# flossjtag.net
KiCad netlist of a schematic drawn in EAGLE
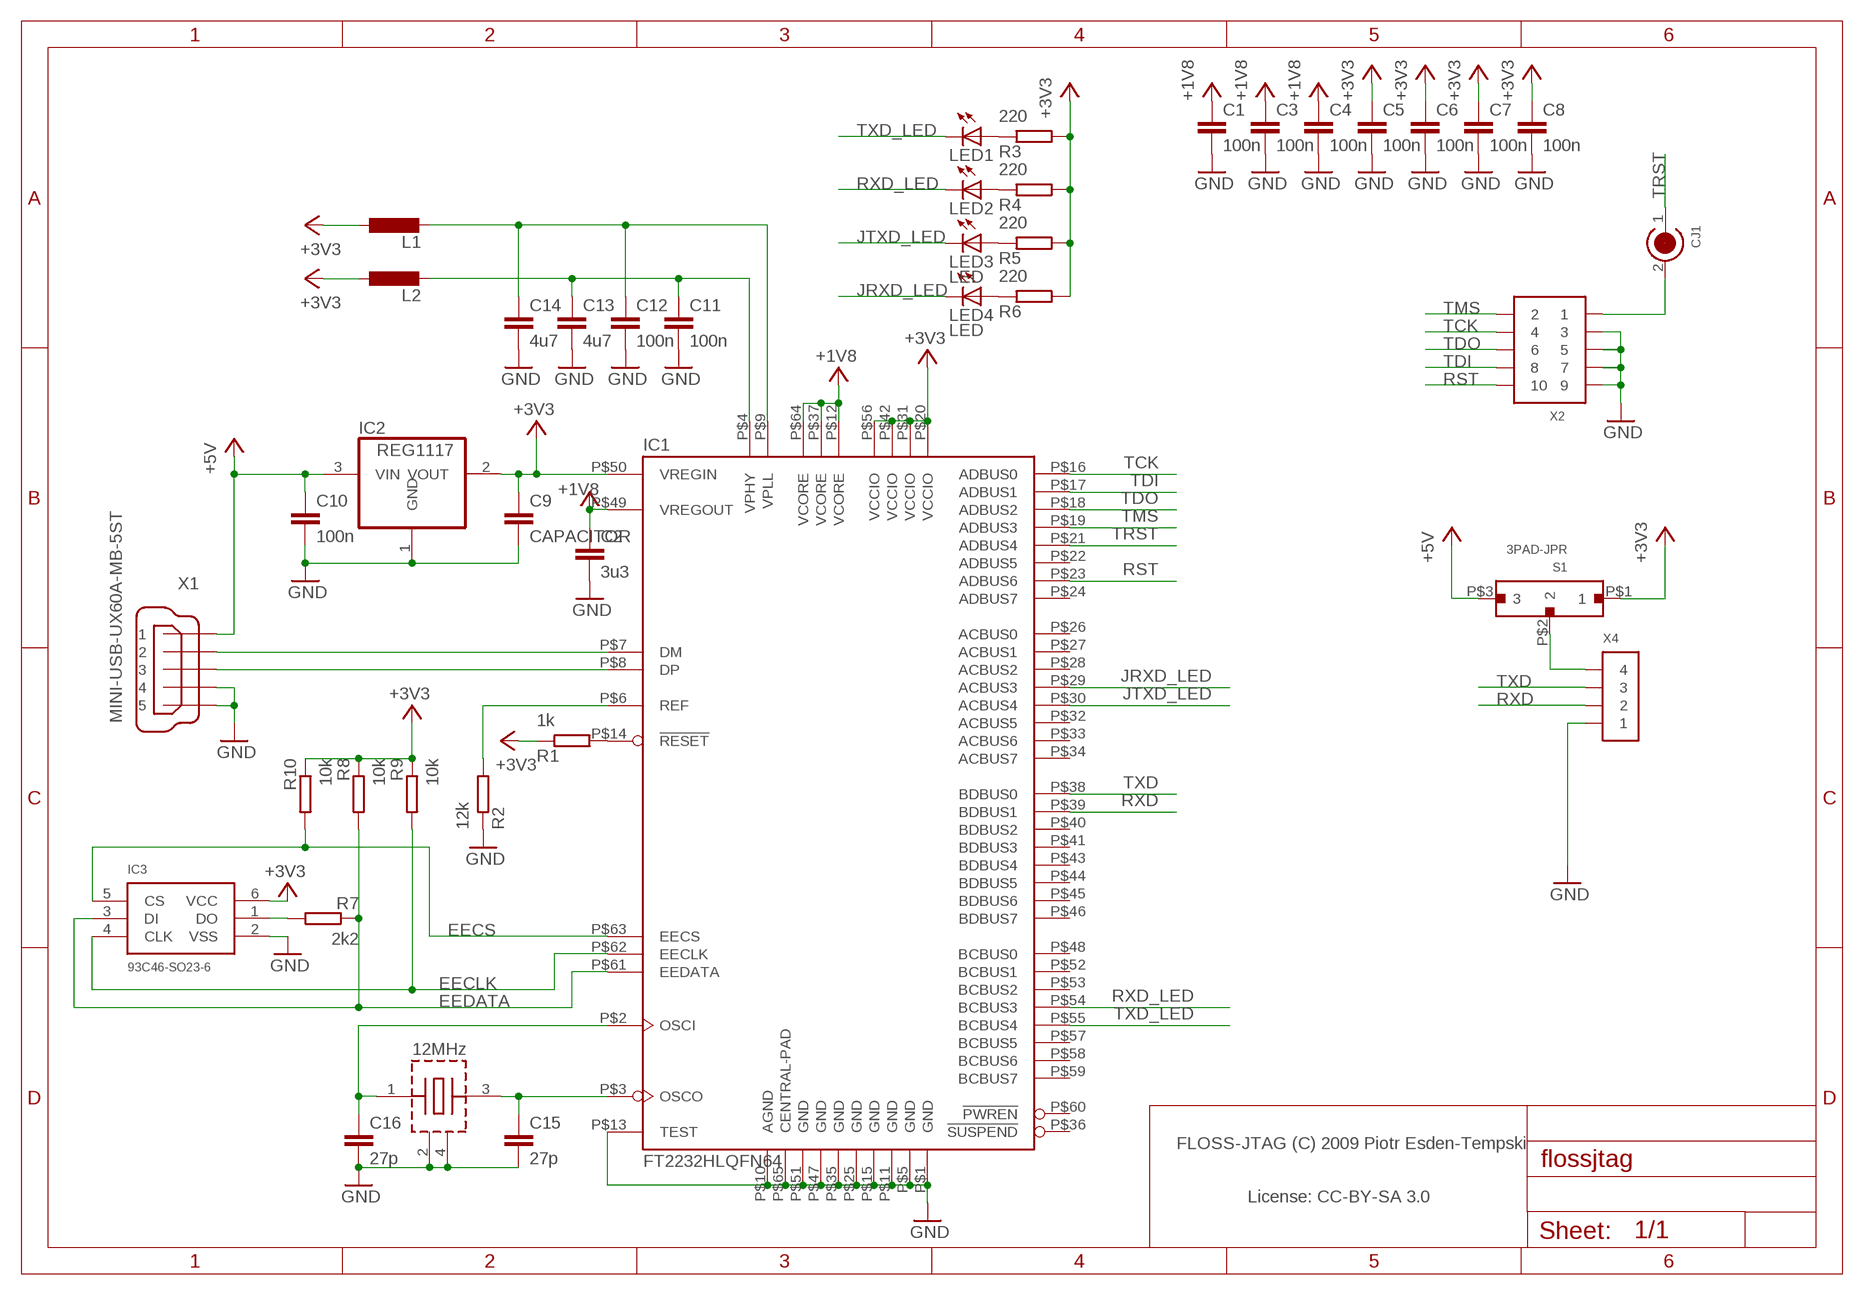
[diagram p0: schematic, sheet 1]

(export (version "E")
  (design (tool "Eeschema 10.0.6"))
  (components
    (comp (ref "C1")
      (value "100n")
      (footprint "eagle-import:0603-CAP")
      (libsource (lib "eagle-import") (part "CAPACITOR-0603"))
    )
    (comp (ref "C2")
      (value "3u3")
      (footprint "eagle-import:0603-CAP")
      (libsource (lib "eagle-import") (part "CAPACITOR-0603"))
    )
    (comp (ref "C3")
      (value "100n")
      (footprint "eagle-import:0603-CAP")
      (libsource (lib "eagle-import") (part "CAPACITOR-0603"))
    )
    (comp (ref "C4")
      (value "100n")
      (footprint "eagle-import:0603-CAP")
      (libsource (lib "eagle-import") (part "CAPACITOR-0603"))
    )
    (comp (ref "C5")
      (value "100n")
      (footprint "eagle-import:0603-CAP")
      (libsource (lib "eagle-import") (part "CAPACITOR-0603"))
    )
    (comp (ref "C6")
      (value "100n")
      (footprint "eagle-import:0603-CAP")
      (libsource (lib "eagle-import") (part "CAPACITOR-0603"))
    )
    (comp (ref "C7")
      (value "100n")
      (footprint "eagle-import:0603-CAP")
      (libsource (lib "eagle-import") (part "CAPACITOR-0603"))
    )
    (comp (ref "C8")
      (value "100n")
      (footprint "eagle-import:0603-CAP")
      (libsource (lib "eagle-import") (part "CAPACITOR-0603"))
    )
    (comp (ref "C9")
      (value "CAPACITOR")
      (footprint "eagle-import:0603-CAP")
      (libsource (lib "eagle-import") (part "CAPACITOR"))
    )
    (comp (ref "C10")
      (value "100n")
      (footprint "eagle-import:0603-CAP")
      (libsource (lib "eagle-import") (part "CAPACITOR"))
    )
    (comp (ref "C11")
      (value "100n")
      (footprint "eagle-import:0603-CAP")
      (libsource (lib "eagle-import") (part "CAPACITOR-0603"))
    )
    (comp (ref "C12")
      (value "100n")
      (footprint "eagle-import:0603-CAP")
      (libsource (lib "eagle-import") (part "CAPACITOR-0603"))
    )
    (comp (ref "C13")
      (value "4u7")
      (footprint "eagle-import:0603-CAP")
      (libsource (lib "eagle-import") (part "CAPACITOR-0603"))
    )
    (comp (ref "C14")
      (value "4u7")
      (footprint "eagle-import:0603-CAP")
      (libsource (lib "eagle-import") (part "CAPACITOR-0603"))
    )
    (comp (ref "C15")
      (value "27p")
      (footprint "eagle-import:0603-CAP")
      (libsource (lib "eagle-import") (part "CAPACITOR"))
    )
    (comp (ref "C16")
      (value "27p")
      (footprint "eagle-import:0603-CAP")
      (libsource (lib "eagle-import") (part "CAPACITOR"))
    )
    (comp (ref "CJ1")
      (value "CIRC_JMP")
      (footprint "eagle-import:CIRC_JMP")
      (libsource (lib "eagle-import") (part "CIRC_JMP"))
    )
    (comp (ref "IC1")
      (value "FT2232HLQFN64")
      (footprint "eagle-import:QFN64")
      (libsource (lib "eagle-import") (part "FT2232HLQFN64"))
    )
    (comp (ref "IC2")
      (value "REG1117")
      (footprint "eagle-import:SOT223")
      (libsource (lib "eagle-import") (part "REG1117"))
    )
    (comp (ref "IC3")
      (value "93C46-SO23-6")
      (footprint "eagle-import:SO23-6")
      (libsource (lib "eagle-import") (part "93C46-SO23-6"))
    )
    (comp (ref "L1")
      (value "INDUCTOR-0603")
      (footprint "eagle-import:0603-IND")
      (libsource (lib "eagle-import") (part "INDUCTOR-0603"))
    )
    (comp (ref "L2")
      (value "INDUCTOR-0603")
      (footprint "eagle-import:0603-IND")
      (libsource (lib "eagle-import") (part "INDUCTOR-0603"))
    )
    (comp (ref "LED1")
      (value "LED")
      (footprint "eagle-import:0603-LED")
      (libsource (lib "eagle-import") (part "LED"))
    )
    (comp (ref "LED2")
      (value "LED")
      (footprint "eagle-import:0603-LED")
      (libsource (lib "eagle-import") (part "LED"))
    )
    (comp (ref "LED3")
      (value "LED")
      (footprint "eagle-import:0603-LED")
      (libsource (lib "eagle-import") (part "LED"))
    )
    (comp (ref "LED4")
      (value "LED")
      (footprint "eagle-import:0603-LED")
      (libsource (lib "eagle-import") (part "LED"))
    )
    (comp (ref "R1")
      (value "1k")
      (footprint "eagle-import:0603-RES")
      (libsource (lib "eagle-import") (part "RESISTOR-0603"))
    )
    (comp (ref "R2")
      (value "12k")
      (footprint "eagle-import:0603-RES")
      (libsource (lib "eagle-import") (part "RESISTOR-0603"))
    )
    (comp (ref "R3")
      (value "220")
      (footprint "eagle-import:0603-RES")
      (libsource (lib "eagle-import") (part "RESISTOR-0603"))
    )
    (comp (ref "R4")
      (value "220")
      (footprint "eagle-import:0603-RES")
      (libsource (lib "eagle-import") (part "RESISTOR-0603"))
    )
    (comp (ref "R5")
      (value "220")
      (footprint "eagle-import:0603-RES")
      (libsource (lib "eagle-import") (part "RESISTOR-0603"))
    )
    (comp (ref "R6")
      (value "220")
      (footprint "eagle-import:0603-RES")
      (libsource (lib "eagle-import") (part "RESISTOR-0603"))
    )
    (comp (ref "R7")
      (value "2k2")
      (footprint "eagle-import:0603-RES")
      (libsource (lib "eagle-import") (part "RESISTOR-0603"))
    )
    (comp (ref "R8")
      (value "10k")
      (footprint "eagle-import:0603-RES")
      (libsource (lib "eagle-import") (part "RESISTOR-0603"))
    )
    (comp (ref "R9")
      (value "10k")
      (footprint "eagle-import:0603-RES")
      (libsource (lib "eagle-import") (part "RESISTOR-0603"))
    )
    (comp (ref "R10")
      (value "10k")
      (footprint "eagle-import:0603-RES")
      (libsource (lib "eagle-import") (part "RESISTOR-0603"))
    )
    (comp (ref "S1")
      (value "3PAD-JPR")
      (footprint "eagle-import:SW-JS102000SAQN")
      (libsource (lib "eagle-import") (part "3PAD-JPR"))
    )
    (comp (ref "X1")
      (value "MINI-USB-UX60A-MB-5ST")
      (footprint "eagle-import:UX60A-MB-5ST")
      (libsource (lib "eagle-import") (part "MINI-USB-UX60A-MB-5ST"))
    )
    (comp (ref "X2")
      (value "CONN_5-2-FTSH-V")
      (footprint "eagle-import:FTSH-105-DV")
      (libsource (lib "eagle-import") (part "CONN_5-2-FTSH-V"))
    )
    (comp (ref "X3")
      (value "12MHz")
      (footprint "eagle-import:NX3225SA")
      (libsource (lib "eagle-import") (part "NX3225SA"))
    )
    (comp (ref "X4")
      (value "CONN_4-1")
      (footprint "eagle-import:PB-53261-04")
      (libsource (lib "eagle-import") (part "CONN_4-1"))
    )
  )
  (nets
    (net (code "1") (name "+1V8") (class "Default")
      (node (ref "C1") (pin "P$1") (pinfunction "1_P$1") (pintype "passive"))
      (node (ref "C2") (pin "P$1") (pinfunction "1_P$1") (pintype "passive"))
      (node (ref "C3") (pin "P$1") (pinfunction "1_P$1") (pintype "passive"))
      (node (ref "C4") (pin "P$1") (pinfunction "1_P$1") (pintype "passive"))
      (node (ref "IC1") (pin "P$12") (pinfunction "VCORE_P$12") (pintype "bidirectional"))
      (node (ref "IC1") (pin "P$37") (pinfunction "VCORE_P$37") (pintype "bidirectional"))
      (node (ref "IC1") (pin "P$49") (pinfunction "VREGOUT_P$49") (pintype "bidirectional"))
      (node (ref "IC1") (pin "P$64") (pinfunction "VCORE_P$64") (pintype "bidirectional"))
    )
    (net (code "2") (name "+3V3") (class "Default")
      (node (ref "C5") (pin "P$1") (pinfunction "1_P$1") (pintype "passive"))
      (node (ref "C6") (pin "P$1") (pinfunction "1_P$1") (pintype "passive"))
      (node (ref "C7") (pin "P$1") (pinfunction "1_P$1") (pintype "passive"))
      (node (ref "C8") (pin "P$1") (pinfunction "1_P$1") (pintype "passive"))
      (node (ref "C9") (pin "P$1") (pinfunction "1_P$1") (pintype "passive"))
      (node (ref "IC1") (pin "P$20") (pinfunction "VCCIO_P$20") (pintype "bidirectional"))
      (node (ref "IC1") (pin "P$31") (pinfunction "VCCIO_P$31") (pintype "bidirectional"))
      (node (ref "IC1") (pin "P$42") (pinfunction "VCCIO_P$42") (pintype "bidirectional"))
      (node (ref "IC1") (pin "P$50") (pinfunction "VREGIN_P$50") (pintype "bidirectional"))
      (node (ref "IC1") (pin "P$56") (pinfunction "VCCIO_P$56") (pintype "bidirectional"))
      (node (ref "IC2") (pin "2") (pinfunction "VOUT_2") (pintype "output"))
      (node (ref "IC3") (pin "6") (pinfunction "VCC_6") (pintype "bidirectional"))
      (node (ref "L1") (pin "P$1") (pinfunction "1_P$1") (pintype "passive"))
      (node (ref "L2") (pin "P$1") (pinfunction "1_P$1") (pintype "passive"))
      (node (ref "R1") (pin "P$1") (pinfunction "1_P$1") (pintype "passive"))
      (node (ref "R10") (pin "P$1") (pinfunction "1_P$1") (pintype "passive"))
      (node (ref "R3") (pin "P$2") (pinfunction "2_P$2") (pintype "passive"))
      (node (ref "R4") (pin "P$2") (pinfunction "2_P$2") (pintype "passive"))
      (node (ref "R5") (pin "P$2") (pinfunction "2_P$2") (pintype "passive"))
      (node (ref "R6") (pin "P$2") (pinfunction "2_P$2") (pintype "passive"))
      (node (ref "R8") (pin "P$1") (pinfunction "1_P$1") (pintype "passive"))
      (node (ref "R9") (pin "P$1") (pinfunction "1_P$1") (pintype "passive"))
      (node (ref "S1") (pin "P$1") (pinfunction "1_P$1") (pintype "passive"))
    )
    (net (code "3") (name "+5V") (class "Default")
      (node (ref "C10") (pin "P$1") (pinfunction "1_P$1") (pintype "passive"))
      (node (ref "IC2") (pin "3") (pinfunction "VIN_3") (pintype "input"))
      (node (ref "S1") (pin "P$3") (pinfunction "3_P$3") (pintype "passive"))
      (node (ref "X1") (pin "1") (pinfunction "1_1") (pintype "input"))
    )
    (net (code "4") (name "/EECLK") (class "Default")
      (node (ref "IC1") (pin "P$62") (pinfunction "EECLK_P$62") (pintype "bidirectional"))
      (node (ref "IC3") (pin "4") (pinfunction "CLK_4") (pintype "bidirectional"))
      (node (ref "R9") (pin "P$2") (pinfunction "2_P$2") (pintype "passive"))
    )
    (net (code "5") (name "/EECS") (class "Default")
      (node (ref "IC1") (pin "P$63") (pinfunction "EECS_P$63") (pintype "bidirectional"))
      (node (ref "IC3") (pin "5") (pinfunction "CS_5") (pintype "bidirectional"))
      (node (ref "R10") (pin "P$2") (pinfunction "2_P$2") (pintype "passive"))
    )
    (net (code "6") (name "/EEDATA") (class "Default")
      (node (ref "IC1") (pin "P$61") (pinfunction "EEDATA_P$61") (pintype "bidirectional"))
      (node (ref "IC3") (pin "3") (pinfunction "DI_3") (pintype "bidirectional"))
      (node (ref "R7") (pin "P$1") (pinfunction "1_P$1") (pintype "passive"))
      (node (ref "R8") (pin "P$2") (pinfunction "2_P$2") (pintype "passive"))
    )
    (net (code "7") (name "/JRXD_LED") (class "Default")
      (node (ref "IC1") (pin "P$29") (pinfunction "ACBUS3_P$29") (pintype "bidirectional"))
      (node (ref "LED4") (pin "C") (pinfunction "C_C") (pintype "passive"))
    )
    (net (code "8") (name "/JTXD_LED") (class "Default")
      (node (ref "IC1") (pin "P$30") (pinfunction "ACBUS4_P$30") (pintype "bidirectional"))
      (node (ref "LED3") (pin "C") (pinfunction "C_C") (pintype "passive"))
    )
    (net (code "9") (name "/RST") (class "Default")
      (node (ref "IC1") (pin "P$23") (pinfunction "ADBUS6_P$23") (pintype "bidirectional"))
      (node (ref "X2") (pin "10") (pinfunction "10_10") (pintype "bidirectional"))
    )
    (net (code "10") (name "/RXD") (class "Default")
      (node (ref "IC1") (pin "P$39") (pinfunction "BDBUS1_P$39") (pintype "bidirectional"))
      (node (ref "X4") (pin "2") (pinfunction "2_2") (pintype "bidirectional"))
    )
    (net (code "11") (name "/RXD_LED") (class "Default")
      (node (ref "IC1") (pin "P$54") (pinfunction "BCBUS3_P$54") (pintype "bidirectional"))
      (node (ref "LED2") (pin "C") (pinfunction "C_C") (pintype "passive"))
    )
    (net (code "12") (name "/TCK") (class "Default")
      (node (ref "IC1") (pin "P$16") (pinfunction "ADBUS0_P$16") (pintype "bidirectional"))
      (node (ref "X2") (pin "4") (pinfunction "4_4") (pintype "bidirectional"))
    )
    (net (code "13") (name "/TDI") (class "Default")
      (node (ref "IC1") (pin "P$17") (pinfunction "ADBUS1_P$17") (pintype "bidirectional"))
      (node (ref "X2") (pin "8") (pinfunction "8_8") (pintype "bidirectional"))
    )
    (net (code "14") (name "/TDO") (class "Default")
      (node (ref "IC1") (pin "P$18") (pinfunction "ADBUS2_P$18") (pintype "bidirectional"))
      (node (ref "X2") (pin "6") (pinfunction "6_6") (pintype "bidirectional"))
    )
    (net (code "15") (name "/TMS") (class "Default")
      (node (ref "IC1") (pin "P$19") (pinfunction "ADBUS3_P$19") (pintype "bidirectional"))
      (node (ref "X2") (pin "2") (pinfunction "2_2") (pintype "bidirectional"))
    )
    (net (code "16") (name "/TRST") (class "Default")
      (node (ref "CJ1") (pin "1") (pinfunction "P$1_1") (pintype "bidirectional"))
      (node (ref "IC1") (pin "P$21") (pinfunction "ADBUS4_P$21") (pintype "bidirectional"))
    )
    (net (code "17") (name "/TXD") (class "Default")
      (node (ref "IC1") (pin "P$38") (pinfunction "BDBUS0_P$38") (pintype "bidirectional"))
      (node (ref "X4") (pin "3") (pinfunction "3_3") (pintype "bidirectional"))
    )
    (net (code "18") (name "/TXD_LED") (class "Default")
      (node (ref "IC1") (pin "P$55") (pinfunction "BCBUS4_P$55") (pintype "bidirectional"))
      (node (ref "LED1") (pin "C") (pinfunction "C_C") (pintype "passive"))
    )
    (net (code "19") (name "GND") (class "Default")
      (node (ref "C1") (pin "P$2") (pinfunction "2_P$2") (pintype "passive"))
      (node (ref "C10") (pin "P$2") (pinfunction "2_P$2") (pintype "passive"))
      (node (ref "C11") (pin "P$2") (pinfunction "2_P$2") (pintype "passive"))
      (node (ref "C12") (pin "P$2") (pinfunction "2_P$2") (pintype "passive"))
      (node (ref "C13") (pin "P$2") (pinfunction "2_P$2") (pintype "passive"))
      (node (ref "C14") (pin "P$2") (pinfunction "2_P$2") (pintype "passive"))
      (node (ref "C15") (pin "P$2") (pinfunction "2_P$2") (pintype "passive"))
      (node (ref "C16") (pin "P$2") (pinfunction "2_P$2") (pintype "passive"))
      (node (ref "C2") (pin "P$2") (pinfunction "2_P$2") (pintype "passive"))
      (node (ref "C3") (pin "P$2") (pinfunction "2_P$2") (pintype "passive"))
      (node (ref "C4") (pin "P$2") (pinfunction "2_P$2") (pintype "passive"))
      (node (ref "C5") (pin "P$2") (pinfunction "2_P$2") (pintype "passive"))
      (node (ref "C6") (pin "P$2") (pinfunction "2_P$2") (pintype "passive"))
      (node (ref "C7") (pin "P$2") (pinfunction "2_P$2") (pintype "passive"))
      (node (ref "C8") (pin "P$2") (pinfunction "2_P$2") (pintype "passive"))
      (node (ref "C9") (pin "P$2") (pinfunction "2_P$2") (pintype "passive"))
      (node (ref "IC1") (pin "P$1") (pinfunction "GND_P$1") (pintype "bidirectional"))
      (node (ref "IC1") (pin "P$10") (pinfunction "AGND_P$10") (pintype "bidirectional"))
      (node (ref "IC1") (pin "P$11") (pinfunction "GND_P$11") (pintype "bidirectional"))
      (node (ref "IC1") (pin "P$13") (pinfunction "TEST_P$13") (pintype "bidirectional"))
      (node (ref "IC1") (pin "P$15") (pinfunction "GND_P$15") (pintype "bidirectional"))
      (node (ref "IC1") (pin "P$25") (pinfunction "GND_P$25") (pintype "bidirectional"))
      (node (ref "IC1") (pin "P$35") (pinfunction "GND_P$35") (pintype "bidirectional"))
      (node (ref "IC1") (pin "P$47") (pinfunction "GND_P$47") (pintype "bidirectional"))
      (node (ref "IC1") (pin "P$5") (pinfunction "GND_P$5") (pintype "bidirectional"))
      (node (ref "IC1") (pin "P$51") (pinfunction "GND_P$51") (pintype "bidirectional"))
      (node (ref "IC1") (pin "P$65") (pinfunction "CENTRAL-PAD_P$65") (pintype "bidirectional"))
      (node (ref "IC2") (pin "1") (pinfunction "GND_1") (pintype "power_in"))
      (node (ref "IC3") (pin "2") (pinfunction "VSS_2") (pintype "bidirectional"))
      (node (ref "R2") (pin "P$1") (pinfunction "1_P$1") (pintype "passive"))
      (node (ref "X1") (pin "4") (pinfunction "4_4") (pintype "input"))
      (node (ref "X1") (pin "5") (pinfunction "5_5") (pintype "input"))
      (node (ref "X2") (pin "3") (pinfunction "3_3") (pintype "bidirectional"))
      (node (ref "X2") (pin "5") (pinfunction "5_5") (pintype "bidirectional"))
      (node (ref "X2") (pin "7") (pinfunction "7_7") (pintype "bidirectional"))
      (node (ref "X2") (pin "9") (pinfunction "9_9") (pintype "bidirectional"))
      (node (ref "X3") (pin "2") (pinfunction "GND_2") (pintype "bidirectional"))
      (node (ref "X3") (pin "4") (pinfunction "GND_4") (pintype "bidirectional"))
      (node (ref "X4") (pin "1") (pinfunction "1_1") (pintype "bidirectional"))
    )
    (net (code "20") (name "Net-(C11-1)") (class "Default")
      (node (ref "C11") (pin "P$1") (pinfunction "1_P$1") (pintype "passive"))
      (node (ref "C13") (pin "P$1") (pinfunction "1_P$1") (pintype "passive"))
      (node (ref "IC1") (pin "P$4") (pinfunction "VPHY_P$4") (pintype "bidirectional"))
      (node (ref "L2") (pin "P$2") (pinfunction "2_P$2") (pintype "passive"))
    )
    (net (code "21") (name "Net-(C12-1)") (class "Default")
      (node (ref "C12") (pin "P$1") (pinfunction "1_P$1") (pintype "passive"))
      (node (ref "C14") (pin "P$1") (pinfunction "1_P$1") (pintype "passive"))
      (node (ref "IC1") (pin "P$9") (pinfunction "VPLL_P$9") (pintype "bidirectional"))
      (node (ref "L1") (pin "P$2") (pinfunction "2_P$2") (pintype "passive"))
    )
    (net (code "22") (name "Net-(C15-1)") (class "Default")
      (node (ref "C15") (pin "P$1") (pinfunction "1_P$1") (pintype "passive"))
      (node (ref "IC1") (pin "P$3") (pinfunction "OSCO_P$3") (pintype "bidirectional"))
      (node (ref "X3") (pin "3") (pinfunction "XTAL_3") (pintype "bidirectional"))
    )
    (net (code "23") (name "Net-(C16-1)") (class "Default")
      (node (ref "C16") (pin "P$1") (pinfunction "1_P$1") (pintype "passive"))
      (node (ref "IC1") (pin "P$2") (pinfunction "OSCI_P$2") (pintype "bidirectional"))
      (node (ref "X3") (pin "1") (pinfunction "XTAL_1") (pintype "bidirectional"))
    )
    (net (code "24") (name "Net-(CJ1-P$2)") (class "Default")
      (node (ref "CJ1") (pin "2") (pinfunction "P$2_2") (pintype "bidirectional"))
      (node (ref "X2") (pin "1") (pinfunction "1_1") (pintype "bidirectional"))
    )
    (net (code "25") (name "Net-(IC1-DM)") (class "Default")
      (node (ref "IC1") (pin "P$7") (pinfunction "DM_P$7") (pintype "bidirectional"))
      (node (ref "X1") (pin "2") (pinfunction "2_2") (pintype "input"))
    )
    (net (code "26") (name "Net-(IC1-DP)") (class "Default")
      (node (ref "IC1") (pin "P$8") (pinfunction "DP_P$8") (pintype "bidirectional"))
      (node (ref "X1") (pin "3") (pinfunction "3_3") (pintype "input"))
    )
    (net (code "27") (name "Net-(IC1-REF)") (class "Default")
      (node (ref "IC1") (pin "P$6") (pinfunction "REF_P$6") (pintype "bidirectional"))
      (node (ref "R2") (pin "P$2") (pinfunction "2_P$2") (pintype "passive"))
    )
    (net (code "28") (name "Net-(IC1-~{RESET})") (class "Default")
      (node (ref "IC1") (pin "P$14") (pinfunction "~{RESET}_P$14") (pintype "bidirectional"))
      (node (ref "R1") (pin "P$2") (pinfunction "2_P$2") (pintype "passive"))
    )
    (net (code "29") (name "Net-(IC3-DO)") (class "Default")
      (node (ref "IC3") (pin "1") (pinfunction "DO_1") (pintype "bidirectional"))
      (node (ref "R7") (pin "P$2") (pinfunction "2_P$2") (pintype "passive"))
    )
    (net (code "30") (name "Net-(R3-1)") (class "Default")
      (node (ref "LED1") (pin "A") (pinfunction "A_A") (pintype "passive"))
      (node (ref "R3") (pin "P$1") (pinfunction "1_P$1") (pintype "passive"))
    )
    (net (code "31") (name "Net-(R4-1)") (class "Default")
      (node (ref "LED2") (pin "A") (pinfunction "A_A") (pintype "passive"))
      (node (ref "R4") (pin "P$1") (pinfunction "1_P$1") (pintype "passive"))
    )
    (net (code "32") (name "Net-(R5-1)") (class "Default")
      (node (ref "LED3") (pin "A") (pinfunction "A_A") (pintype "passive"))
      (node (ref "R5") (pin "P$1") (pinfunction "1_P$1") (pintype "passive"))
    )
    (net (code "33") (name "Net-(R6-1)") (class "Default")
      (node (ref "LED4") (pin "A") (pinfunction "A_A") (pintype "passive"))
      (node (ref "R6") (pin "P$1") (pinfunction "1_P$1") (pintype "passive"))
    )
    (net (code "34") (name "Net-(S1-2)") (class "Default")
      (node (ref "S1") (pin "P$2") (pinfunction "2_P$2") (pintype "passive"))
      (node (ref "X4") (pin "4") (pinfunction "4_4") (pintype "bidirectional"))
    )
    (net (code "35") (name "unconnected-(IC1-ACBUS0-PadP$26)") (class "Default")
      (node (ref "IC1") (pin "P$26") (pinfunction "ACBUS0_P$26") (pintype "bidirectional"))
    )
    (net (code "36") (name "unconnected-(IC1-ACBUS1-PadP$27)") (class "Default")
      (node (ref "IC1") (pin "P$27") (pinfunction "ACBUS1_P$27") (pintype "bidirectional"))
    )
    (net (code "37") (name "unconnected-(IC1-ACBUS2-PadP$28)") (class "Default")
      (node (ref "IC1") (pin "P$28") (pinfunction "ACBUS2_P$28") (pintype "bidirectional"))
    )
    (net (code "38") (name "unconnected-(IC1-ACBUS5-PadP$32)") (class "Default")
      (node (ref "IC1") (pin "P$32") (pinfunction "ACBUS5_P$32") (pintype "bidirectional"))
    )
    (net (code "39") (name "unconnected-(IC1-ACBUS6-PadP$33)") (class "Default")
      (node (ref "IC1") (pin "P$33") (pinfunction "ACBUS6_P$33") (pintype "bidirectional"))
    )
    (net (code "40") (name "unconnected-(IC1-ACBUS7-PadP$34)") (class "Default")
      (node (ref "IC1") (pin "P$34") (pinfunction "ACBUS7_P$34") (pintype "bidirectional"))
    )
    (net (code "41") (name "unconnected-(IC1-ADBUS5-PadP$22)") (class "Default")
      (node (ref "IC1") (pin "P$22") (pinfunction "ADBUS5_P$22") (pintype "bidirectional"))
    )
    (net (code "42") (name "unconnected-(IC1-ADBUS7-PadP$24)") (class "Default")
      (node (ref "IC1") (pin "P$24") (pinfunction "ADBUS7_P$24") (pintype "bidirectional"))
    )
    (net (code "43") (name "unconnected-(IC1-BCBUS0-PadP$48)") (class "Default")
      (node (ref "IC1") (pin "P$48") (pinfunction "BCBUS0_P$48") (pintype "bidirectional"))
    )
    (net (code "44") (name "unconnected-(IC1-BCBUS1-PadP$52)") (class "Default")
      (node (ref "IC1") (pin "P$52") (pinfunction "BCBUS1_P$52") (pintype "bidirectional"))
    )
    (net (code "45") (name "unconnected-(IC1-BCBUS2-PadP$53)") (class "Default")
      (node (ref "IC1") (pin "P$53") (pinfunction "BCBUS2_P$53") (pintype "bidirectional"))
    )
    (net (code "46") (name "unconnected-(IC1-BCBUS5-PadP$57)") (class "Default")
      (node (ref "IC1") (pin "P$57") (pinfunction "BCBUS5_P$57") (pintype "bidirectional"))
    )
    (net (code "47") (name "unconnected-(IC1-BCBUS6-PadP$58)") (class "Default")
      (node (ref "IC1") (pin "P$58") (pinfunction "BCBUS6_P$58") (pintype "bidirectional"))
    )
    (net (code "48") (name "unconnected-(IC1-BCBUS7-PadP$59)") (class "Default")
      (node (ref "IC1") (pin "P$59") (pinfunction "BCBUS7_P$59") (pintype "bidirectional"))
    )
    (net (code "49") (name "unconnected-(IC1-BDBUS2-PadP$40)") (class "Default")
      (node (ref "IC1") (pin "P$40") (pinfunction "BDBUS2_P$40") (pintype "bidirectional"))
    )
    (net (code "50") (name "unconnected-(IC1-BDBUS3-PadP$41)") (class "Default")
      (node (ref "IC1") (pin "P$41") (pinfunction "BDBUS3_P$41") (pintype "bidirectional"))
    )
    (net (code "51") (name "unconnected-(IC1-BDBUS4-PadP$43)") (class "Default")
      (node (ref "IC1") (pin "P$43") (pinfunction "BDBUS4_P$43") (pintype "bidirectional"))
    )
    (net (code "52") (name "unconnected-(IC1-BDBUS5-PadP$44)") (class "Default")
      (node (ref "IC1") (pin "P$44") (pinfunction "BDBUS5_P$44") (pintype "bidirectional"))
    )
    (net (code "53") (name "unconnected-(IC1-BDBUS6-PadP$45)") (class "Default")
      (node (ref "IC1") (pin "P$45") (pinfunction "BDBUS6_P$45") (pintype "bidirectional"))
    )
    (net (code "54") (name "unconnected-(IC1-BDBUS7-PadP$46)") (class "Default")
      (node (ref "IC1") (pin "P$46") (pinfunction "BDBUS7_P$46") (pintype "bidirectional"))
    )
    (net (code "55") (name "unconnected-(IC1-~{PWREN}-PadP$60)") (class "Default")
      (node (ref "IC1") (pin "P$60") (pinfunction "~{PWREN}_P$60") (pintype "bidirectional"))
    )
    (net (code "56") (name "unconnected-(IC1-~{SUSPEND}-PadP$36)") (class "Default")
      (node (ref "IC1") (pin "P$36") (pinfunction "~{SUSPEND}_P$36") (pintype "bidirectional"))
    )
  )
)
